# Solar_Array_Design.net
KiCad netlist of a schematic drawn in EAGLE
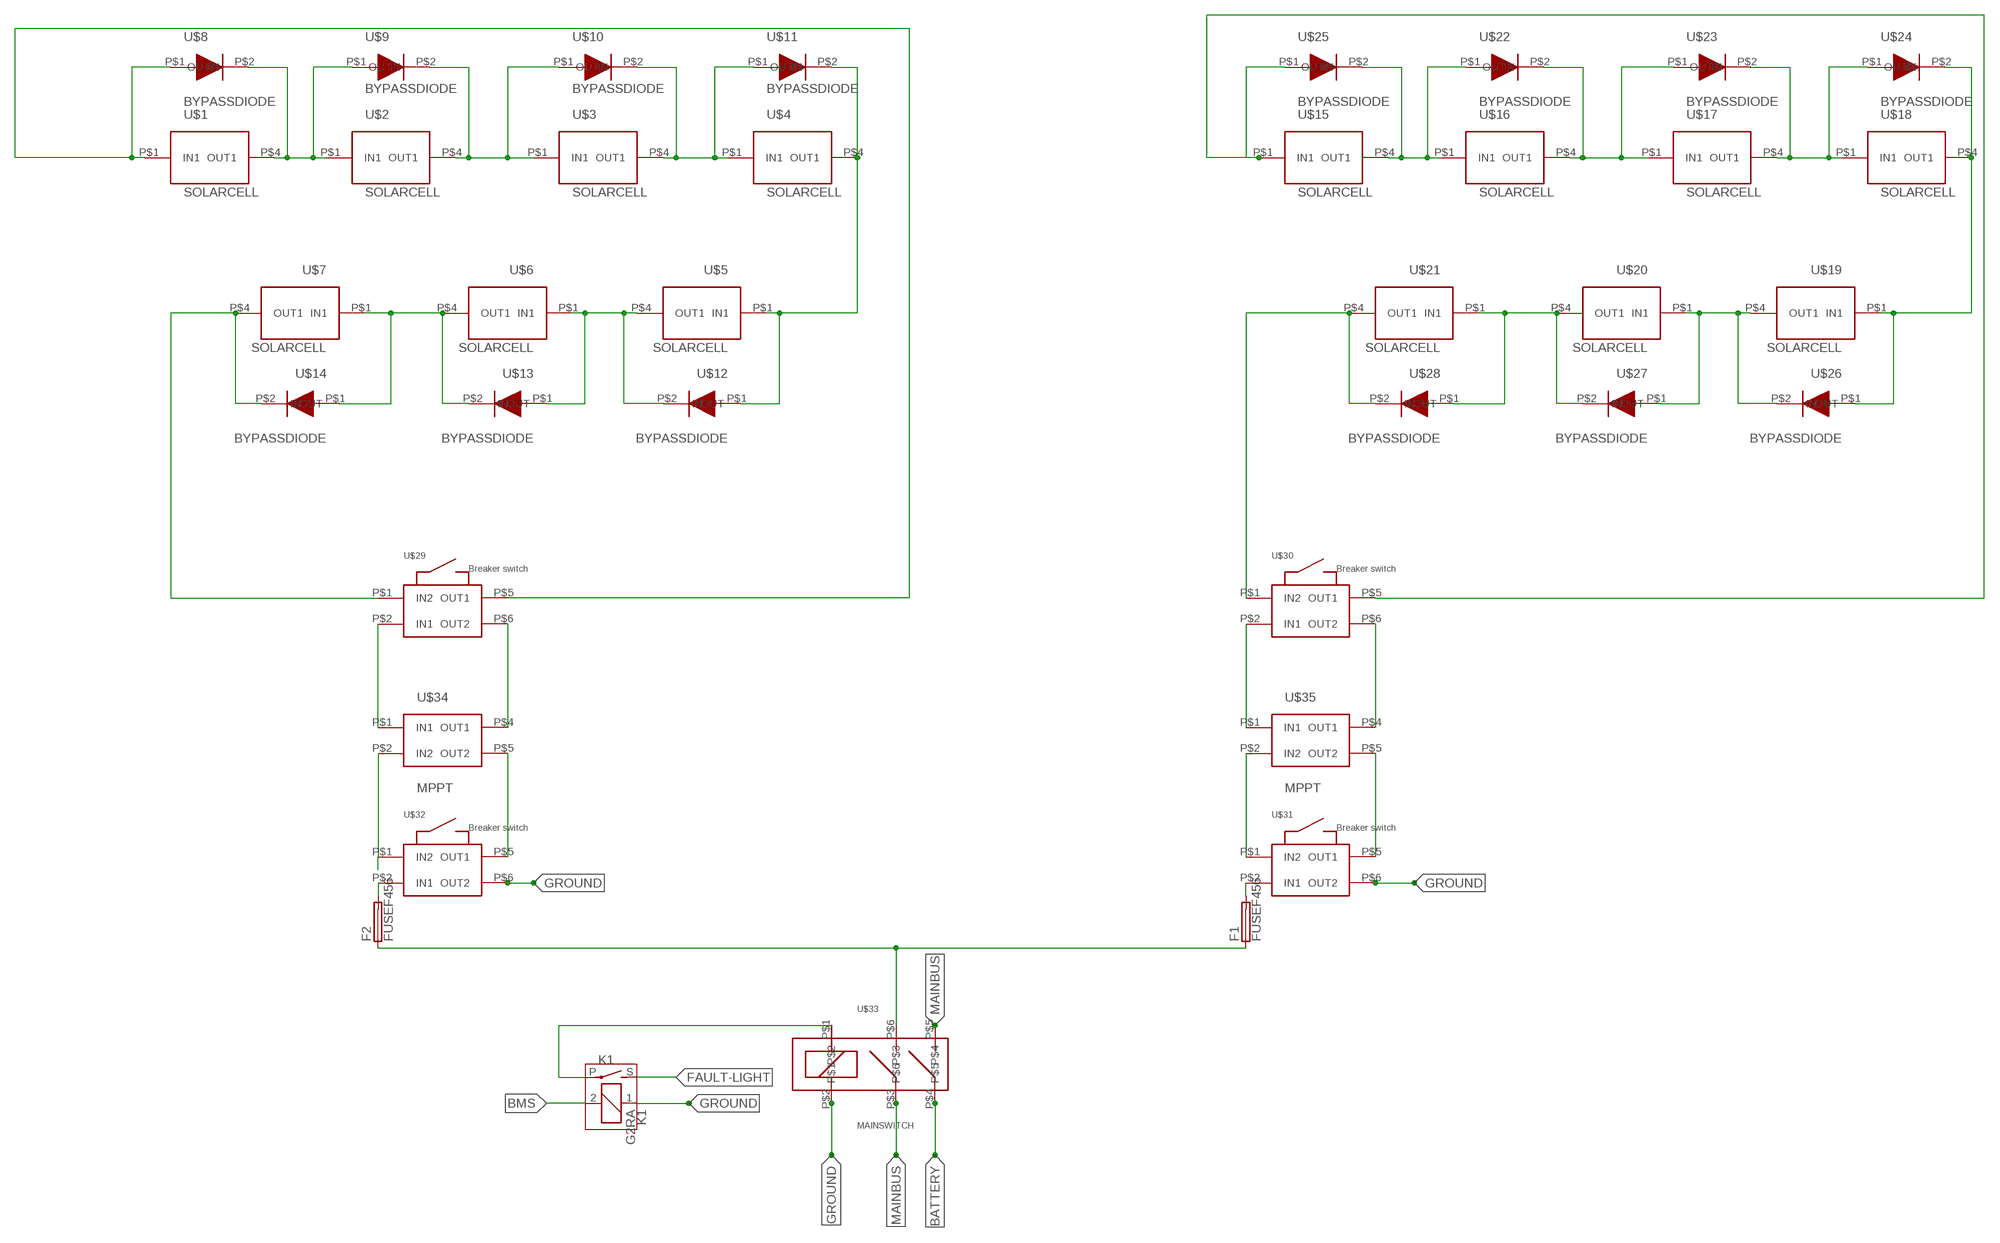
[diagram p0: schematic, sheet 1]

(export (version "E")
  (design (tool "Eeschema 10.0.6"))
  (components
    (comp (ref "F1")
      (value "FUSEF456")
      (footprint "eagle-import:F456")
      (libsource (lib "eagle-import") (part "FUSEF456"))
    )
    (comp (ref "F2")
      (value "FUSEF456")
      (footprint "eagle-import:F456")
      (libsource (lib "eagle-import") (part "FUSEF456"))
    )
    (comp (ref "K1")
      (value "G2RA")
      (footprint "eagle-import:G2RA")
      (libsource (lib "eagle-import") (part "G2RA"))
    )
    (comp (ref "U$1")
      (value "SOLARCELL")
      (footprint "eagle-import:SOLARCELL")
      (libsource (lib "eagle-import") (part "SOLARCELL"))
    )
    (comp (ref "U$2")
      (value "SOLARCELL")
      (footprint "eagle-import:SOLARCELL")
      (libsource (lib "eagle-import") (part "SOLARCELL"))
    )
    (comp (ref "U$3")
      (value "SOLARCELL")
      (footprint "eagle-import:SOLARCELL")
      (libsource (lib "eagle-import") (part "SOLARCELL"))
    )
    (comp (ref "U$4")
      (value "SOLARCELL")
      (footprint "eagle-import:SOLARCELL")
      (libsource (lib "eagle-import") (part "SOLARCELL"))
    )
    (comp (ref "U$5")
      (value "SOLARCELL")
      (footprint "eagle-import:SOLARCELL")
      (libsource (lib "eagle-import") (part "SOLARCELL"))
    )
    (comp (ref "U$6")
      (value "SOLARCELL")
      (footprint "eagle-import:SOLARCELL")
      (libsource (lib "eagle-import") (part "SOLARCELL"))
    )
    (comp (ref "U$7")
      (value "SOLARCELL")
      (footprint "eagle-import:SOLARCELL")
      (libsource (lib "eagle-import") (part "SOLARCELL"))
    )
    (comp (ref "U$8")
      (value "BYPASSDIODE")
      (footprint "eagle-import:BYPASSDIODE")
      (libsource (lib "eagle-import") (part "BYPASSDIODE"))
    )
    (comp (ref "U$9")
      (value "BYPASSDIODE")
      (footprint "eagle-import:BYPASSDIODE")
      (libsource (lib "eagle-import") (part "BYPASSDIODE"))
    )
    (comp (ref "U$10")
      (value "BYPASSDIODE")
      (footprint "eagle-import:BYPASSDIODE")
      (libsource (lib "eagle-import") (part "BYPASSDIODE"))
    )
    (comp (ref "U$11")
      (value "BYPASSDIODE")
      (footprint "eagle-import:BYPASSDIODE")
      (libsource (lib "eagle-import") (part "BYPASSDIODE"))
    )
    (comp (ref "U$12")
      (value "BYPASSDIODE")
      (footprint "eagle-import:BYPASSDIODE")
      (libsource (lib "eagle-import") (part "BYPASSDIODE"))
    )
    (comp (ref "U$13")
      (value "BYPASSDIODE")
      (footprint "eagle-import:BYPASSDIODE")
      (libsource (lib "eagle-import") (part "BYPASSDIODE"))
    )
    (comp (ref "U$14")
      (value "BYPASSDIODE")
      (footprint "eagle-import:BYPASSDIODE")
      (libsource (lib "eagle-import") (part "BYPASSDIODE"))
    )
    (comp (ref "U$15")
      (value "SOLARCELL")
      (footprint "eagle-import:SOLARCELL")
      (libsource (lib "eagle-import") (part "SOLARCELL"))
    )
    (comp (ref "U$16")
      (value "SOLARCELL")
      (footprint "eagle-import:SOLARCELL")
      (libsource (lib "eagle-import") (part "SOLARCELL"))
    )
    (comp (ref "U$17")
      (value "SOLARCELL")
      (footprint "eagle-import:SOLARCELL")
      (libsource (lib "eagle-import") (part "SOLARCELL"))
    )
    (comp (ref "U$18")
      (value "SOLARCELL")
      (footprint "eagle-import:SOLARCELL")
      (libsource (lib "eagle-import") (part "SOLARCELL"))
    )
    (comp (ref "U$19")
      (value "SOLARCELL")
      (footprint "eagle-import:SOLARCELL")
      (libsource (lib "eagle-import") (part "SOLARCELL"))
    )
    (comp (ref "U$20")
      (value "SOLARCELL")
      (footprint "eagle-import:SOLARCELL")
      (libsource (lib "eagle-import") (part "SOLARCELL"))
    )
    (comp (ref "U$21")
      (value "SOLARCELL")
      (footprint "eagle-import:SOLARCELL")
      (libsource (lib "eagle-import") (part "SOLARCELL"))
    )
    (comp (ref "U$22")
      (value "BYPASSDIODE")
      (footprint "eagle-import:BYPASSDIODE")
      (libsource (lib "eagle-import") (part "BYPASSDIODE"))
    )
    (comp (ref "U$23")
      (value "BYPASSDIODE")
      (footprint "eagle-import:BYPASSDIODE")
      (libsource (lib "eagle-import") (part "BYPASSDIODE"))
    )
    (comp (ref "U$24")
      (value "BYPASSDIODE")
      (footprint "eagle-import:BYPASSDIODE")
      (libsource (lib "eagle-import") (part "BYPASSDIODE"))
    )
    (comp (ref "U$25")
      (value "BYPASSDIODE")
      (footprint "eagle-import:BYPASSDIODE")
      (libsource (lib "eagle-import") (part "BYPASSDIODE"))
    )
    (comp (ref "U$26")
      (value "BYPASSDIODE")
      (footprint "eagle-import:BYPASSDIODE")
      (libsource (lib "eagle-import") (part "BYPASSDIODE"))
    )
    (comp (ref "U$27")
      (value "BYPASSDIODE")
      (footprint "eagle-import:BYPASSDIODE")
      (libsource (lib "eagle-import") (part "BYPASSDIODE"))
    )
    (comp (ref "U$28")
      (value "BYPASSDIODE")
      (footprint "eagle-import:BYPASSDIODE")
      (libsource (lib "eagle-import") (part "BYPASSDIODE"))
    )
    (comp (ref "U$29")
      (value "CIRCUITBREAKER")
      (footprint "eagle-import:CIRUITBREAKER")
      (libsource (lib "eagle-import") (part "CIRCUITBREAKER"))
    )
    (comp (ref "U$30")
      (value "CIRCUITBREAKER")
      (footprint "eagle-import:CIRUITBREAKER")
      (libsource (lib "eagle-import") (part "CIRCUITBREAKER"))
    )
    (comp (ref "U$31")
      (value "CIRCUITBREAKER")
      (footprint "eagle-import:CIRUITBREAKER")
      (libsource (lib "eagle-import") (part "CIRCUITBREAKER"))
    )
    (comp (ref "U$32")
      (value "CIRCUITBREAKER")
      (footprint "eagle-import:CIRUITBREAKER")
      (libsource (lib "eagle-import") (part "CIRCUITBREAKER"))
    )
    (comp (ref "U$33")
      (value "MAINSWITCH")
      (footprint "eagle-import:MAINSWITCH")
      (libsource (lib "eagle-import") (part "MAINSWITCH"))
    )
    (comp (ref "U$34")
      (value "MPPT")
      (footprint "eagle-import:MPPT")
      (libsource (lib "eagle-import") (part "MPPT"))
    )
    (comp (ref "U$35")
      (value "MPPT")
      (footprint "eagle-import:MPPT")
      (libsource (lib "eagle-import") (part "MPPT"))
    )
  )
  (nets
    (net (code "1") (name "BATTERY") (class "Default")
      (node (ref "U$33") (pin "P$4") (pinfunction "P$4_P$4") (pintype "bidirectional"))
    )
    (net (code "2") (name "BMS") (class "Default")
      (node (ref "K1") (pin "2") (pinfunction "2_2") (pintype "passive"))
    )
    (net (code "3") (name "FAULT-LIGHT") (class "Default")
      (node (ref "K1") (pin "S") (pinfunction "S_S") (pintype "passive"))
    )
    (net (code "4") (name "GROUND") (class "Default")
      (node (ref "K1") (pin "1") (pinfunction "1_1") (pintype "passive"))
      (node (ref "U$31") (pin "P$6") (pinfunction "OUT2_P$6") (pintype "bidirectional"))
      (node (ref "U$32") (pin "P$6") (pinfunction "OUT2_P$6") (pintype "bidirectional"))
      (node (ref "U$33") (pin "P$2") (pinfunction "P$2_P$2") (pintype "bidirectional"))
    )
    (net (code "5") (name "MAINBUS") (class "Default")
      (node (ref "U$33") (pin "P$3") (pinfunction "P$3_P$3") (pintype "bidirectional"))
      (node (ref "U$33") (pin "P$5") (pinfunction "P$5_P$5") (pintype "bidirectional"))
    )
    (net (code "6") (name "Net-(F1-Pad1)") (class "Default")
      (node (ref "F1") (pin "1") (pinfunction "1_1") (pintype "passive"))
      (node (ref "F2") (pin "1") (pinfunction "1_1") (pintype "passive"))
      (node (ref "U$33") (pin "P$6") (pinfunction "P$6_P$6") (pintype "bidirectional"))
    )
    (net (code "7") (name "Net-(K1-PadP)") (class "Default")
      (node (ref "K1") (pin "P") (pinfunction "P_P") (pintype "passive"))
      (node (ref "U$33") (pin "P$1") (pinfunction "P$1_P$1") (pintype "bidirectional"))
    )
    (net (code "8") (name "Net-(U$1-IN1)") (class "Default")
      (node (ref "U$1") (pin "P$1") (pinfunction "IN1_P$1") (pintype "bidirectional"))
      (node (ref "U$29") (pin "P$5") (pinfunction "OUT1_P$5") (pintype "bidirectional"))
      (node (ref "U$8") (pin "P$1") (pinfunction "IN_P$1") (pintype "bidirectional"))
    )
    (net (code "9") (name "Net-(U$1-OUT1)") (class "Default")
      (node (ref "U$1") (pin "P$4") (pinfunction "OUT1_P$4") (pintype "bidirectional"))
      (node (ref "U$2") (pin "P$1") (pinfunction "IN1_P$1") (pintype "bidirectional"))
      (node (ref "U$8") (pin "P$2") (pinfunction "OUT_P$2") (pintype "bidirectional"))
      (node (ref "U$9") (pin "P$1") (pinfunction "IN_P$1") (pintype "bidirectional"))
    )
    (net (code "10") (name "Net-(U$10-IN)") (class "Default")
      (node (ref "U$10") (pin "P$1") (pinfunction "IN_P$1") (pintype "bidirectional"))
      (node (ref "U$2") (pin "P$4") (pinfunction "OUT1_P$4") (pintype "bidirectional"))
      (node (ref "U$3") (pin "P$1") (pinfunction "IN1_P$1") (pintype "bidirectional"))
      (node (ref "U$9") (pin "P$2") (pinfunction "OUT_P$2") (pintype "bidirectional"))
    )
    (net (code "11") (name "Net-(U$10-OUT)") (class "Default")
      (node (ref "U$10") (pin "P$2") (pinfunction "OUT_P$2") (pintype "bidirectional"))
      (node (ref "U$11") (pin "P$1") (pinfunction "IN_P$1") (pintype "bidirectional"))
      (node (ref "U$3") (pin "P$4") (pinfunction "OUT1_P$4") (pintype "bidirectional"))
      (node (ref "U$4") (pin "P$1") (pinfunction "IN1_P$1") (pintype "bidirectional"))
    )
    (net (code "12") (name "Net-(U$11-OUT)") (class "Default")
      (node (ref "U$11") (pin "P$2") (pinfunction "OUT_P$2") (pintype "bidirectional"))
      (node (ref "U$12") (pin "P$1") (pinfunction "IN_P$1") (pintype "bidirectional"))
      (node (ref "U$4") (pin "P$4") (pinfunction "OUT1_P$4") (pintype "bidirectional"))
      (node (ref "U$5") (pin "P$1") (pinfunction "IN1_P$1") (pintype "bidirectional"))
    )
    (net (code "13") (name "Net-(U$12-OUT)") (class "Default")
      (node (ref "U$12") (pin "P$2") (pinfunction "OUT_P$2") (pintype "bidirectional"))
      (node (ref "U$13") (pin "P$1") (pinfunction "IN_P$1") (pintype "bidirectional"))
      (node (ref "U$5") (pin "P$4") (pinfunction "OUT1_P$4") (pintype "bidirectional"))
      (node (ref "U$6") (pin "P$1") (pinfunction "IN1_P$1") (pintype "bidirectional"))
    )
    (net (code "14") (name "Net-(U$13-OUT)") (class "Default")
      (node (ref "U$13") (pin "P$2") (pinfunction "OUT_P$2") (pintype "bidirectional"))
      (node (ref "U$14") (pin "P$1") (pinfunction "IN_P$1") (pintype "bidirectional"))
      (node (ref "U$6") (pin "P$4") (pinfunction "OUT1_P$4") (pintype "bidirectional"))
      (node (ref "U$7") (pin "P$1") (pinfunction "IN1_P$1") (pintype "bidirectional"))
    )
    (net (code "15") (name "Net-(U$14-OUT)") (class "Default")
      (node (ref "U$14") (pin "P$2") (pinfunction "OUT_P$2") (pintype "bidirectional"))
      (node (ref "U$29") (pin "P$1") (pinfunction "IN2_P$1") (pintype "bidirectional"))
      (node (ref "U$7") (pin "P$4") (pinfunction "OUT1_P$4") (pintype "bidirectional"))
    )
    (net (code "16") (name "Net-(U$15-IN1)") (class "Default")
      (node (ref "U$15") (pin "P$1") (pinfunction "IN1_P$1") (pintype "bidirectional"))
      (node (ref "U$25") (pin "P$1") (pinfunction "IN_P$1") (pintype "bidirectional"))
      (node (ref "U$30") (pin "P$5") (pinfunction "OUT1_P$5") (pintype "bidirectional"))
    )
    (net (code "17") (name "Net-(U$15-OUT1)") (class "Default")
      (node (ref "U$15") (pin "P$4") (pinfunction "OUT1_P$4") (pintype "bidirectional"))
      (node (ref "U$16") (pin "P$1") (pinfunction "IN1_P$1") (pintype "bidirectional"))
      (node (ref "U$22") (pin "P$1") (pinfunction "IN_P$1") (pintype "bidirectional"))
      (node (ref "U$25") (pin "P$2") (pinfunction "OUT_P$2") (pintype "bidirectional"))
    )
    (net (code "18") (name "Net-(U$16-OUT1)") (class "Default")
      (node (ref "U$16") (pin "P$4") (pinfunction "OUT1_P$4") (pintype "bidirectional"))
      (node (ref "U$17") (pin "P$1") (pinfunction "IN1_P$1") (pintype "bidirectional"))
      (node (ref "U$22") (pin "P$2") (pinfunction "OUT_P$2") (pintype "bidirectional"))
      (node (ref "U$23") (pin "P$1") (pinfunction "IN_P$1") (pintype "bidirectional"))
    )
    (net (code "19") (name "Net-(U$17-OUT1)") (class "Default")
      (node (ref "U$17") (pin "P$4") (pinfunction "OUT1_P$4") (pintype "bidirectional"))
      (node (ref "U$18") (pin "P$1") (pinfunction "IN1_P$1") (pintype "bidirectional"))
      (node (ref "U$23") (pin "P$2") (pinfunction "OUT_P$2") (pintype "bidirectional"))
      (node (ref "U$24") (pin "P$1") (pinfunction "IN_P$1") (pintype "bidirectional"))
    )
    (net (code "20") (name "Net-(U$18-OUT1)") (class "Default")
      (node (ref "U$18") (pin "P$4") (pinfunction "OUT1_P$4") (pintype "bidirectional"))
      (node (ref "U$19") (pin "P$1") (pinfunction "IN1_P$1") (pintype "bidirectional"))
      (node (ref "U$24") (pin "P$2") (pinfunction "OUT_P$2") (pintype "bidirectional"))
      (node (ref "U$26") (pin "P$1") (pinfunction "IN_P$1") (pintype "bidirectional"))
    )
    (net (code "21") (name "Net-(U$19-OUT1)") (class "Default")
      (node (ref "U$19") (pin "P$4") (pinfunction "OUT1_P$4") (pintype "bidirectional"))
      (node (ref "U$20") (pin "P$1") (pinfunction "IN1_P$1") (pintype "bidirectional"))
      (node (ref "U$26") (pin "P$2") (pinfunction "OUT_P$2") (pintype "bidirectional"))
      (node (ref "U$27") (pin "P$1") (pinfunction "IN_P$1") (pintype "bidirectional"))
    )
    (net (code "22") (name "Net-(U$20-OUT1)") (class "Default")
      (node (ref "U$20") (pin "P$4") (pinfunction "OUT1_P$4") (pintype "bidirectional"))
      (node (ref "U$21") (pin "P$1") (pinfunction "IN1_P$1") (pintype "bidirectional"))
      (node (ref "U$27") (pin "P$2") (pinfunction "OUT_P$2") (pintype "bidirectional"))
      (node (ref "U$28") (pin "P$1") (pinfunction "IN_P$1") (pintype "bidirectional"))
    )
    (net (code "23") (name "Net-(U$21-OUT1)") (class "Default")
      (node (ref "U$21") (pin "P$4") (pinfunction "OUT1_P$4") (pintype "bidirectional"))
      (node (ref "U$28") (pin "P$2") (pinfunction "OUT_P$2") (pintype "bidirectional"))
      (node (ref "U$30") (pin "P$1") (pinfunction "IN2_P$1") (pintype "bidirectional"))
    )
    (net (code "24") (name "Net-(U$29-IN1)") (class "Default")
      (node (ref "U$29") (pin "P$2") (pinfunction "IN1_P$2") (pintype "bidirectional"))
      (node (ref "U$34") (pin "P$1") (pinfunction "IN1_P$1") (pintype "bidirectional"))
    )
    (net (code "25") (name "Net-(U$29-OUT2)") (class "Default")
      (node (ref "U$29") (pin "P$6") (pinfunction "OUT2_P$6") (pintype "bidirectional"))
      (node (ref "U$34") (pin "P$4") (pinfunction "OUT1_P$4") (pintype "bidirectional"))
    )
    (net (code "26") (name "Net-(U$30-IN1)") (class "Default")
      (node (ref "U$30") (pin "P$2") (pinfunction "IN1_P$2") (pintype "bidirectional"))
      (node (ref "U$35") (pin "P$1") (pinfunction "IN1_P$1") (pintype "bidirectional"))
    )
    (net (code "27") (name "Net-(U$30-OUT2)") (class "Default")
      (node (ref "U$30") (pin "P$6") (pinfunction "OUT2_P$6") (pintype "bidirectional"))
      (node (ref "U$35") (pin "P$4") (pinfunction "OUT1_P$4") (pintype "bidirectional"))
    )
    (net (code "28") (name "Net-(U$31-IN1)") (class "Default")
      (node (ref "F1") (pin "2") (pinfunction "2_2") (pintype "passive"))
      (node (ref "U$31") (pin "P$2") (pinfunction "IN1_P$2") (pintype "bidirectional"))
    )
    (net (code "29") (name "Net-(U$31-IN2)") (class "Default")
      (node (ref "U$31") (pin "P$1") (pinfunction "IN2_P$1") (pintype "bidirectional"))
      (node (ref "U$35") (pin "P$2") (pinfunction "IN2_P$2") (pintype "bidirectional"))
    )
    (net (code "30") (name "Net-(U$31-OUT1)") (class "Default")
      (node (ref "U$31") (pin "P$5") (pinfunction "OUT1_P$5") (pintype "bidirectional"))
      (node (ref "U$35") (pin "P$5") (pinfunction "OUT2_P$5") (pintype "bidirectional"))
    )
    (net (code "31") (name "Net-(U$32-IN1)") (class "Default")
      (node (ref "F2") (pin "2") (pinfunction "2_2") (pintype "passive"))
      (node (ref "U$32") (pin "P$2") (pinfunction "IN1_P$2") (pintype "bidirectional"))
    )
    (net (code "32") (name "Net-(U$32-IN2)") (class "Default")
      (node (ref "U$32") (pin "P$1") (pinfunction "IN2_P$1") (pintype "bidirectional"))
      (node (ref "U$34") (pin "P$2") (pinfunction "IN2_P$2") (pintype "bidirectional"))
    )
    (net (code "33") (name "Net-(U$32-OUT1)") (class "Default")
      (node (ref "U$32") (pin "P$5") (pinfunction "OUT1_P$5") (pintype "bidirectional"))
      (node (ref "U$34") (pin "P$5") (pinfunction "OUT2_P$5") (pintype "bidirectional"))
    )
  )
)
